# fpga10-serdes-power.net
KiCad netlist of a schematic drawn in Altium Designer
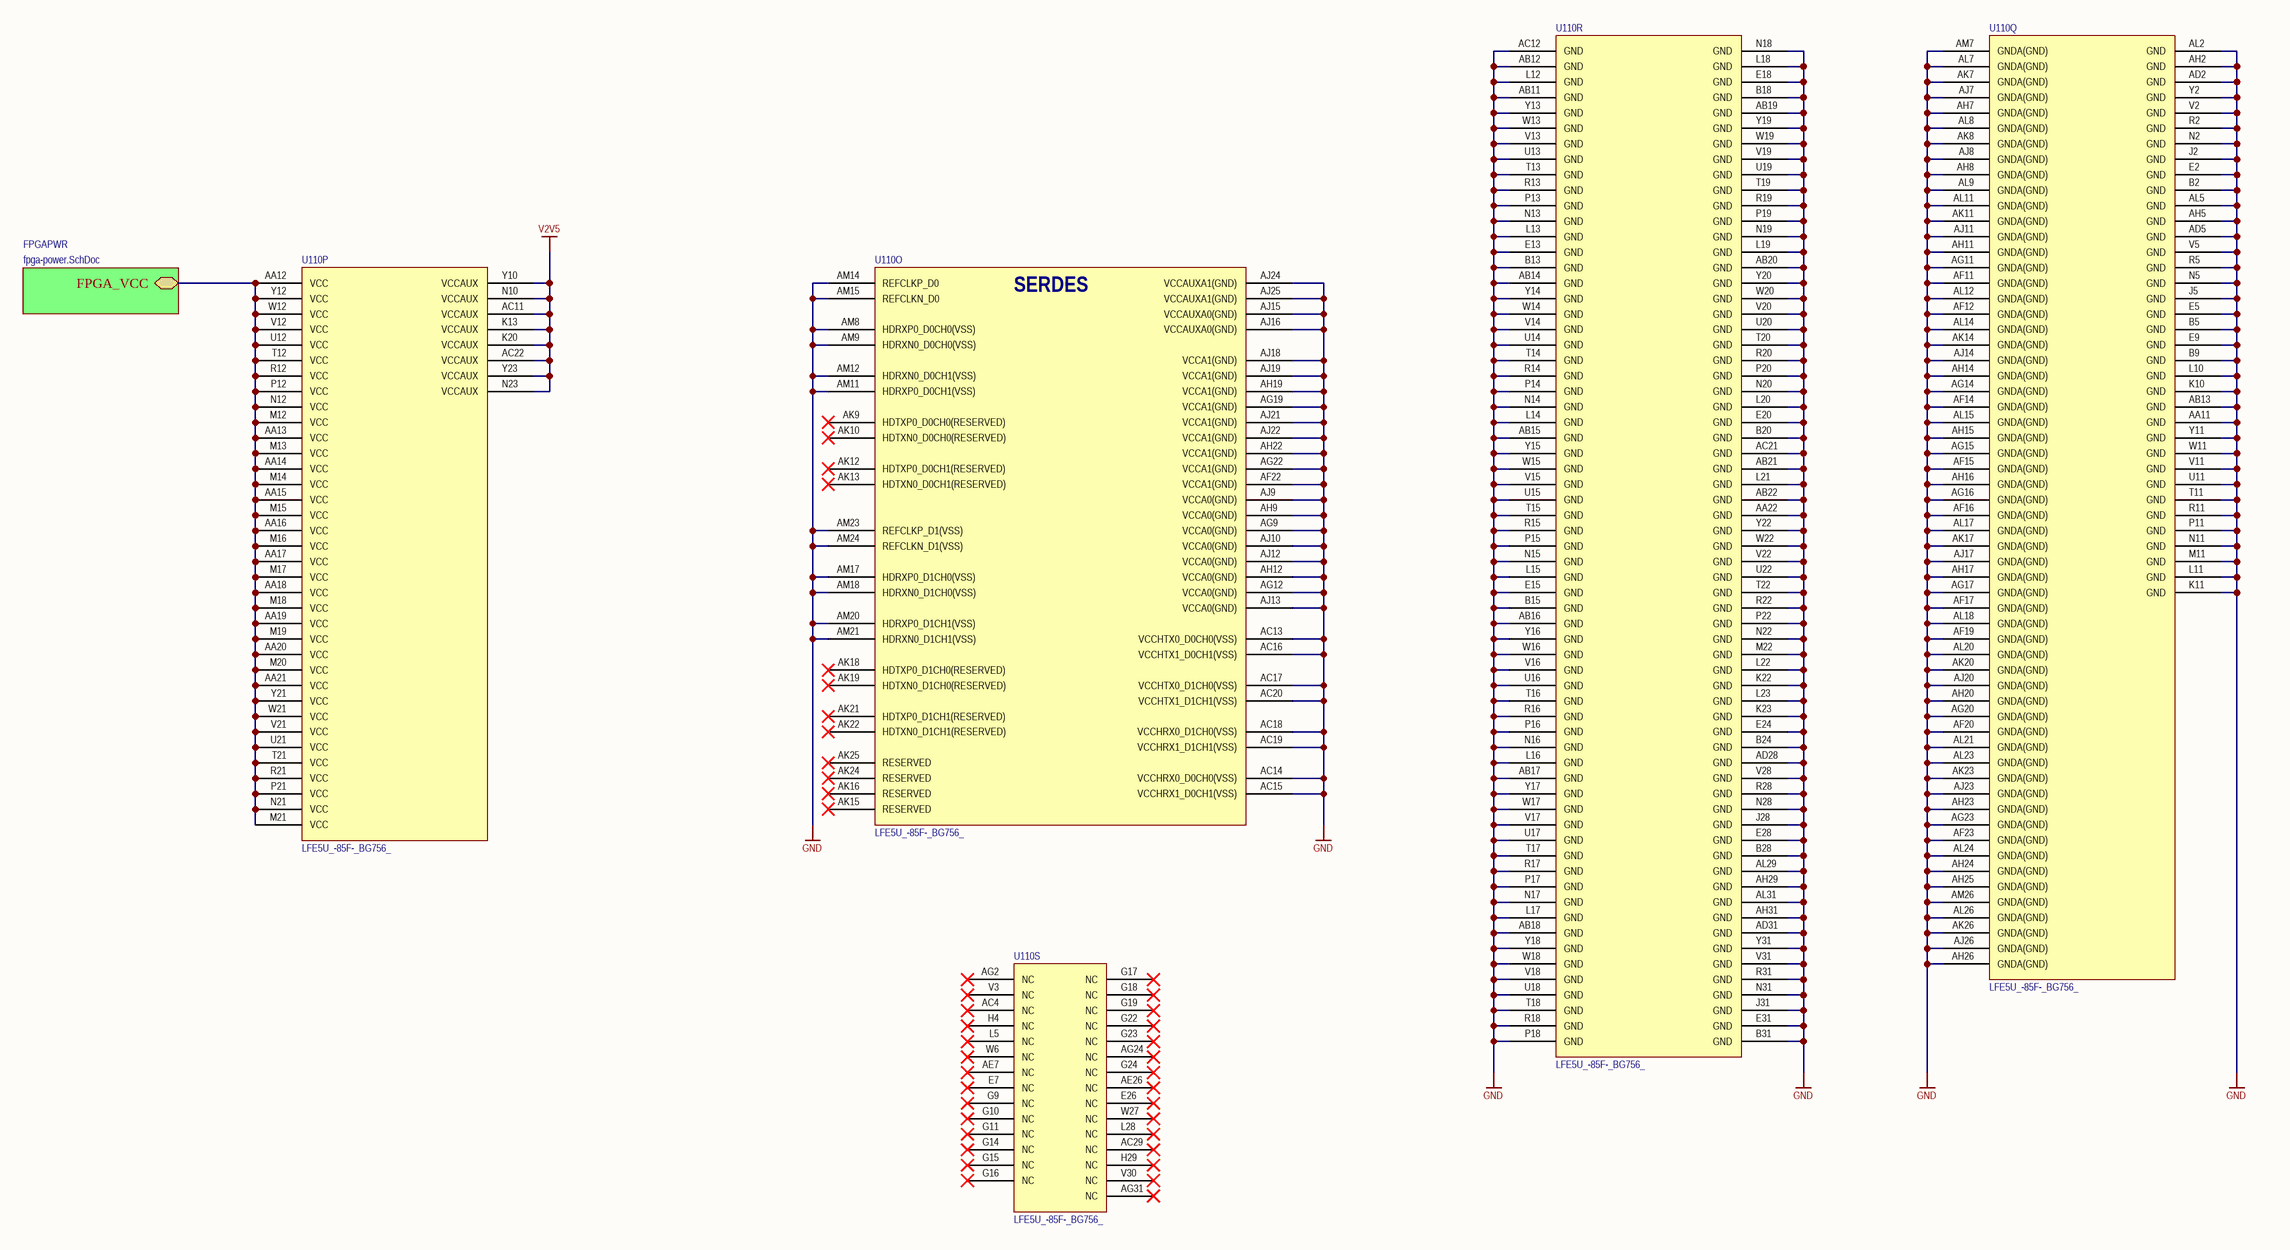
[diagram p0: fpga10-serdes-power.SchDoc]

(export (version "E")
  (design (tool "Eeschema 10.0.6"))
  (components
    (comp (ref "U110")
      (value "LFE5U_-85F-_BG756_")
      (footprint "lattice:caBGA756")
      (description "ECP5 FPGA, 85k LUT, 756-caBGA")
      (fields (field (name "MANUFACTURER") "Lattice Semiconductor"))
      (libsource (lib "lattice") (part "LFE5U_-85F-_BG756_"))
    )
  )
  (nets
    (net (code "1") (name "/FPGA_VCC") (class "Default")
      (node (ref "U110") (pin "AA12") (pinfunction "VCC_AA12") (pintype "power_in"))
      (node (ref "U110") (pin "AA13") (pinfunction "VCC_AA13") (pintype "power_in"))
      (node (ref "U110") (pin "AA14") (pinfunction "VCC_AA14") (pintype "power_in"))
      (node (ref "U110") (pin "AA15") (pinfunction "VCC_AA15") (pintype "power_in"))
      (node (ref "U110") (pin "AA16") (pinfunction "VCC_AA16") (pintype "power_in"))
      (node (ref "U110") (pin "AA17") (pinfunction "VCC_AA17") (pintype "power_in"))
      (node (ref "U110") (pin "AA18") (pinfunction "VCC_AA18") (pintype "power_in"))
      (node (ref "U110") (pin "AA19") (pinfunction "VCC_AA19") (pintype "power_in"))
      (node (ref "U110") (pin "AA20") (pinfunction "VCC_AA20") (pintype "power_in"))
      (node (ref "U110") (pin "AA21") (pinfunction "VCC_AA21") (pintype "power_in"))
      (node (ref "U110") (pin "M12") (pinfunction "VCC_M12") (pintype "power_in"))
      (node (ref "U110") (pin "M13") (pinfunction "VCC_M13") (pintype "power_in"))
      (node (ref "U110") (pin "M14") (pinfunction "VCC_M14") (pintype "power_in"))
      (node (ref "U110") (pin "M15") (pinfunction "VCC_M15") (pintype "power_in"))
      (node (ref "U110") (pin "M16") (pinfunction "VCC_M16") (pintype "power_in"))
      (node (ref "U110") (pin "M17") (pinfunction "VCC_M17") (pintype "power_in"))
      (node (ref "U110") (pin "M18") (pinfunction "VCC_M18") (pintype "power_in"))
      (node (ref "U110") (pin "M19") (pinfunction "VCC_M19") (pintype "power_in"))
      (node (ref "U110") (pin "M20") (pinfunction "VCC_M20") (pintype "power_in"))
      (node (ref "U110") (pin "M21") (pinfunction "VCC_M21") (pintype "power_in"))
      (node (ref "U110") (pin "N12") (pinfunction "VCC_N12") (pintype "power_in"))
      (node (ref "U110") (pin "N21") (pinfunction "VCC_N21") (pintype "power_in"))
      (node (ref "U110") (pin "P12") (pinfunction "VCC_P12") (pintype "power_in"))
      (node (ref "U110") (pin "P21") (pinfunction "VCC_P21") (pintype "power_in"))
      (node (ref "U110") (pin "R12") (pinfunction "VCC_R12") (pintype "power_in"))
      (node (ref "U110") (pin "R21") (pinfunction "VCC_R21") (pintype "power_in"))
      (node (ref "U110") (pin "T12") (pinfunction "VCC_T12") (pintype "power_in"))
      (node (ref "U110") (pin "T21") (pinfunction "VCC_T21") (pintype "power_in"))
      (node (ref "U110") (pin "U12") (pinfunction "VCC_U12") (pintype "power_in"))
      (node (ref "U110") (pin "U21") (pinfunction "VCC_U21") (pintype "power_in"))
      (node (ref "U110") (pin "V12") (pinfunction "VCC_V12") (pintype "power_in"))
      (node (ref "U110") (pin "V21") (pinfunction "VCC_V21") (pintype "power_in"))
      (node (ref "U110") (pin "W12") (pinfunction "VCC_W12") (pintype "power_in"))
      (node (ref "U110") (pin "W21") (pinfunction "VCC_W21") (pintype "power_in"))
      (node (ref "U110") (pin "Y12") (pinfunction "VCC_Y12") (pintype "power_in"))
      (node (ref "U110") (pin "Y21") (pinfunction "VCC_Y21") (pintype "power_in"))
    )
    (net (code "2") (name "GND") (class "Default")
      (node (ref "U110") (pin "AA11") (pinfunction "GND_AA11") (pintype "power_in"))
      (node (ref "U110") (pin "AA22") (pinfunction "GND_AA22") (pintype "power_in"))
      (node (ref "U110") (pin "AB11") (pinfunction "GND_AB11") (pintype "power_in"))
      (node (ref "U110") (pin "AB12") (pinfunction "GND_AB12") (pintype "power_in"))
      (node (ref "U110") (pin "AB13") (pinfunction "GND_AB13") (pintype "power_in"))
      (node (ref "U110") (pin "AB14") (pinfunction "GND_AB14") (pintype "power_in"))
      (node (ref "U110") (pin "AB15") (pinfunction "GND_AB15") (pintype "power_in"))
      (node (ref "U110") (pin "AB16") (pinfunction "GND_AB16") (pintype "power_in"))
      (node (ref "U110") (pin "AB17") (pinfunction "GND_AB17") (pintype "power_in"))
      (node (ref "U110") (pin "AB18") (pinfunction "GND_AB18") (pintype "power_in"))
      (node (ref "U110") (pin "AB19") (pinfunction "GND_AB19") (pintype "power_in"))
      (node (ref "U110") (pin "AB20") (pinfunction "GND_AB20") (pintype "power_in"))
      (node (ref "U110") (pin "AB21") (pinfunction "GND_AB21") (pintype "power_in"))
      (node (ref "U110") (pin "AB22") (pinfunction "GND_AB22") (pintype "power_in"))
      (node (ref "U110") (pin "AC12") (pinfunction "GND_AC12") (pintype "power_in"))
      (node (ref "U110") (pin "AC13") (pinfunction "VCCHTX0_D0CH0(VSS)_AC13") (pintype "power_in"))
      (node (ref "U110") (pin "AC14") (pinfunction "VCCHRX0_D0CH0(VSS)_AC14") (pintype "power_in"))
      (node (ref "U110") (pin "AC15") (pinfunction "VCCHRX1_D0CH1(VSS)_AC15") (pintype "power_in"))
      (node (ref "U110") (pin "AC16") (pinfunction "VCCHTX1_D0CH1(VSS)_AC16") (pintype "power_in"))
      (node (ref "U110") (pin "AC17") (pinfunction "VCCHTX0_D1CH0(VSS)_AC17") (pintype "power_in"))
      (node (ref "U110") (pin "AC18") (pinfunction "VCCHRX0_D1CH0(VSS)_AC18") (pintype "power_in"))
      (node (ref "U110") (pin "AC19") (pinfunction "VCCHRX1_D1CH1(VSS)_AC19") (pintype "power_in"))
      (node (ref "U110") (pin "AC20") (pinfunction "VCCHTX1_D1CH1(VSS)_AC20") (pintype "power_in"))
      (node (ref "U110") (pin "AC21") (pinfunction "GND_AC21") (pintype "power_in"))
      (node (ref "U110") (pin "AD2") (pinfunction "GND_AD2") (pintype "power_in"))
      (node (ref "U110") (pin "AD28") (pinfunction "GND_AD28") (pintype "power_in"))
      (node (ref "U110") (pin "AD31") (pinfunction "GND_AD31") (pintype "power_in"))
      (node (ref "U110") (pin "AD5") (pinfunction "GND_AD5") (pintype "power_in"))
      (node (ref "U110") (pin "AF11") (pinfunction "GNDA(GND)_AF11") (pintype "power_in"))
      (node (ref "U110") (pin "AF12") (pinfunction "GNDA(GND)_AF12") (pintype "power_in"))
      (node (ref "U110") (pin "AF14") (pinfunction "GNDA(GND)_AF14") (pintype "power_in"))
      (node (ref "U110") (pin "AF15") (pinfunction "GNDA(GND)_AF15") (pintype "power_in"))
      (node (ref "U110") (pin "AF16") (pinfunction "GNDA(GND)_AF16") (pintype "power_in"))
      (node (ref "U110") (pin "AF17") (pinfunction "GNDA(GND)_AF17") (pintype "power_in"))
      (node (ref "U110") (pin "AF19") (pinfunction "GNDA(GND)_AF19") (pintype "power_in"))
      (node (ref "U110") (pin "AF20") (pinfunction "GNDA(GND)_AF20") (pintype "power_in"))
      (node (ref "U110") (pin "AF22") (pinfunction "VCCA1(GND)_AF22") (pintype "power_in"))
      (node (ref "U110") (pin "AF23") (pinfunction "GNDA(GND)_AF23") (pintype "power_in"))
      (node (ref "U110") (pin "AG11") (pinfunction "GNDA(GND)_AG11") (pintype "power_in"))
      (node (ref "U110") (pin "AG12") (pinfunction "VCCA0(GND)_AG12") (pintype "power_in"))
      (node (ref "U110") (pin "AG14") (pinfunction "GNDA(GND)_AG14") (pintype "power_in"))
      (node (ref "U110") (pin "AG15") (pinfunction "GNDA(GND)_AG15") (pintype "power_in"))
      (node (ref "U110") (pin "AG16") (pinfunction "GNDA(GND)_AG16") (pintype "power_in"))
      (node (ref "U110") (pin "AG17") (pinfunction "GNDA(GND)_AG17") (pintype "power_in"))
      (node (ref "U110") (pin "AG19") (pinfunction "VCCA1(GND)_AG19") (pintype "power_in"))
      (node (ref "U110") (pin "AG20") (pinfunction "GNDA(GND)_AG20") (pintype "power_in"))
      (node (ref "U110") (pin "AG22") (pinfunction "VCCA1(GND)_AG22") (pintype "power_in"))
      (node (ref "U110") (pin "AG23") (pinfunction "GNDA(GND)_AG23") (pintype "power_in"))
      (node (ref "U110") (pin "AG9") (pinfunction "VCCA0(GND)_AG9") (pintype "power_in"))
      (node (ref "U110") (pin "AH11") (pinfunction "GNDA(GND)_AH11") (pintype "power_in"))
      (node (ref "U110") (pin "AH12") (pinfunction "VCCA0(GND)_AH12") (pintype "power_in"))
      (node (ref "U110") (pin "AH14") (pinfunction "GNDA(GND)_AH14") (pintype "power_in"))
      (node (ref "U110") (pin "AH15") (pinfunction "GNDA(GND)_AH15") (pintype "power_in"))
      (node (ref "U110") (pin "AH16") (pinfunction "GNDA(GND)_AH16") (pintype "power_in"))
      (node (ref "U110") (pin "AH17") (pinfunction "GNDA(GND)_AH17") (pintype "power_in"))
      (node (ref "U110") (pin "AH19") (pinfunction "VCCA1(GND)_AH19") (pintype "power_in"))
      (node (ref "U110") (pin "AH2") (pinfunction "GND_AH2") (pintype "power_in"))
      (node (ref "U110") (pin "AH20") (pinfunction "GNDA(GND)_AH20") (pintype "power_in"))
      (node (ref "U110") (pin "AH22") (pinfunction "VCCA1(GND)_AH22") (pintype "power_in"))
      (node (ref "U110") (pin "AH23") (pinfunction "GNDA(GND)_AH23") (pintype "power_in"))
      (node (ref "U110") (pin "AH24") (pinfunction "GNDA(GND)_AH24") (pintype "power_in"))
      (node (ref "U110") (pin "AH25") (pinfunction "GNDA(GND)_AH25") (pintype "power_in"))
      (node (ref "U110") (pin "AH26") (pinfunction "GNDA(GND)_AH26") (pintype "power_in"))
      (node (ref "U110") (pin "AH29") (pinfunction "GND_AH29") (pintype "power_in"))
      (node (ref "U110") (pin "AH31") (pinfunction "GND_AH31") (pintype "power_in"))
      (node (ref "U110") (pin "AH5") (pinfunction "GND_AH5") (pintype "power_in"))
      (node (ref "U110") (pin "AH7") (pinfunction "GNDA(GND)_AH7") (pintype "power_in"))
      (node (ref "U110") (pin "AH8") (pinfunction "GNDA(GND)_AH8") (pintype "power_in"))
      (node (ref "U110") (pin "AH9") (pinfunction "VCCA0(GND)_AH9") (pintype "power_in"))
      (node (ref "U110") (pin "AJ10") (pinfunction "VCCA0(GND)_AJ10") (pintype "power_in"))
      (node (ref "U110") (pin "AJ11") (pinfunction "GNDA(GND)_AJ11") (pintype "power_in"))
      (node (ref "U110") (pin "AJ12") (pinfunction "VCCA0(GND)_AJ12") (pintype "power_in"))
      (node (ref "U110") (pin "AJ13") (pinfunction "VCCA0(GND)_AJ13") (pintype "power_in"))
      (node (ref "U110") (pin "AJ14") (pinfunction "GNDA(GND)_AJ14") (pintype "power_in"))
      (node (ref "U110") (pin "AJ15") (pinfunction "VCCAUXA0(GND)_AJ15") (pintype "power_in"))
      (node (ref "U110") (pin "AJ16") (pinfunction "VCCAUXA0(GND)_AJ16") (pintype "power_in"))
      (node (ref "U110") (pin "AJ17") (pinfunction "GNDA(GND)_AJ17") (pintype "power_in"))
      (node (ref "U110") (pin "AJ18") (pinfunction "VCCA1(GND)_AJ18") (pintype "power_in"))
      (node (ref "U110") (pin "AJ19") (pinfunction "VCCA1(GND)_AJ19") (pintype "power_in"))
      (node (ref "U110") (pin "AJ20") (pinfunction "GNDA(GND)_AJ20") (pintype "power_in"))
      (node (ref "U110") (pin "AJ21") (pinfunction "VCCA1(GND)_AJ21") (pintype "power_in"))
      (node (ref "U110") (pin "AJ22") (pinfunction "VCCA1(GND)_AJ22") (pintype "power_in"))
      (node (ref "U110") (pin "AJ23") (pinfunction "GNDA(GND)_AJ23") (pintype "power_in"))
      (node (ref "U110") (pin "AJ24") (pinfunction "VCCAUXA1(GND)_AJ24") (pintype "power_in"))
      (node (ref "U110") (pin "AJ25") (pinfunction "VCCAUXA1(GND)_AJ25") (pintype "power_in"))
      (node (ref "U110") (pin "AJ26") (pinfunction "GNDA(GND)_AJ26") (pintype "power_in"))
      (node (ref "U110") (pin "AJ7") (pinfunction "GNDA(GND)_AJ7") (pintype "power_in"))
      (node (ref "U110") (pin "AJ8") (pinfunction "GNDA(GND)_AJ8") (pintype "power_in"))
      (node (ref "U110") (pin "AJ9") (pinfunction "VCCA0(GND)_AJ9") (pintype "power_in"))
      (node (ref "U110") (pin "AK11") (pinfunction "GNDA(GND)_AK11") (pintype "power_in"))
      (node (ref "U110") (pin "AK14") (pinfunction "GNDA(GND)_AK14") (pintype "power_in"))
      (node (ref "U110") (pin "AK17") (pinfunction "GNDA(GND)_AK17") (pintype "power_in"))
      (node (ref "U110") (pin "AK20") (pinfunction "GNDA(GND)_AK20") (pintype "power_in"))
      (node (ref "U110") (pin "AK23") (pinfunction "GNDA(GND)_AK23") (pintype "power_in"))
      (node (ref "U110") (pin "AK26") (pinfunction "GNDA(GND)_AK26") (pintype "power_in"))
      (node (ref "U110") (pin "AK7") (pinfunction "GNDA(GND)_AK7") (pintype "power_in"))
      (node (ref "U110") (pin "AK8") (pinfunction "GNDA(GND)_AK8") (pintype "power_in"))
      (node (ref "U110") (pin "AL11") (pinfunction "GNDA(GND)_AL11") (pintype "power_in"))
      (node (ref "U110") (pin "AL12") (pinfunction "GNDA(GND)_AL12") (pintype "power_in"))
      (node (ref "U110") (pin "AL14") (pinfunction "GNDA(GND)_AL14") (pintype "power_in"))
      (node (ref "U110") (pin "AL15") (pinfunction "GNDA(GND)_AL15") (pintype "power_in"))
      (node (ref "U110") (pin "AL17") (pinfunction "GNDA(GND)_AL17") (pintype "power_in"))
      (node (ref "U110") (pin "AL18") (pinfunction "GNDA(GND)_AL18") (pintype "power_in"))
      (node (ref "U110") (pin "AL2") (pinfunction "GND_AL2") (pintype "power_in"))
      (node (ref "U110") (pin "AL20") (pinfunction "GNDA(GND)_AL20") (pintype "power_in"))
      (node (ref "U110") (pin "AL21") (pinfunction "GNDA(GND)_AL21") (pintype "power_in"))
      (node (ref "U110") (pin "AL23") (pinfunction "GNDA(GND)_AL23") (pintype "power_in"))
      (node (ref "U110") (pin "AL24") (pinfunction "GNDA(GND)_AL24") (pintype "power_in"))
      (node (ref "U110") (pin "AL26") (pinfunction "GNDA(GND)_AL26") (pintype "power_in"))
      (node (ref "U110") (pin "AL29") (pinfunction "GND_AL29") (pintype "power_in"))
      (node (ref "U110") (pin "AL31") (pinfunction "GND_AL31") (pintype "power_in"))
      (node (ref "U110") (pin "AL5") (pinfunction "GND_AL5") (pintype "power_in"))
      (node (ref "U110") (pin "AL7") (pinfunction "GNDA(GND)_AL7") (pintype "power_in"))
      (node (ref "U110") (pin "AL8") (pinfunction "GNDA(GND)_AL8") (pintype "power_in"))
      (node (ref "U110") (pin "AL9") (pinfunction "GNDA(GND)_AL9") (pintype "power_in"))
      (node (ref "U110") (pin "AM11") (pinfunction "HDRXP0_D0CH1(VSS)_AM11") (pintype "passive"))
      (node (ref "U110") (pin "AM12") (pinfunction "HDRXN0_D0CH1(VSS)_AM12") (pintype "passive"))
      (node (ref "U110") (pin "AM14") (pinfunction "REFCLKP_D0_AM14") (pintype "passive"))
      (node (ref "U110") (pin "AM15") (pinfunction "REFCLKN_D0_AM15") (pintype "passive"))
      (node (ref "U110") (pin "AM17") (pinfunction "HDRXP0_D1CH0(VSS)_AM17") (pintype "passive"))
      (node (ref "U110") (pin "AM18") (pinfunction "HDRXN0_D1CH0(VSS)_AM18") (pintype "passive"))
      (node (ref "U110") (pin "AM20") (pinfunction "HDRXP0_D1CH1(VSS)_AM20") (pintype "passive"))
      (node (ref "U110") (pin "AM21") (pinfunction "HDRXN0_D1CH1(VSS)_AM21") (pintype "passive"))
      (node (ref "U110") (pin "AM23") (pinfunction "REFCLKP_D1(VSS)_AM23") (pintype "passive"))
      (node (ref "U110") (pin "AM24") (pinfunction "REFCLKN_D1(VSS)_AM24") (pintype "passive"))
      (node (ref "U110") (pin "AM26") (pinfunction "GNDA(GND)_AM26") (pintype "power_in"))
      (node (ref "U110") (pin "AM7") (pinfunction "GNDA(GND)_AM7") (pintype "power_in"))
      (node (ref "U110") (pin "AM8") (pinfunction "HDRXP0_D0CH0(VSS)_AM8") (pintype "passive"))
      (node (ref "U110") (pin "AM9") (pinfunction "HDRXN0_D0CH0(VSS)_AM9") (pintype "passive"))
      (node (ref "U110") (pin "B13") (pinfunction "GND_B13") (pintype "power_in"))
      (node (ref "U110") (pin "B15") (pinfunction "GND_B15") (pintype "power_in"))
      (node (ref "U110") (pin "B18") (pinfunction "GND_B18") (pintype "power_in"))
      (node (ref "U110") (pin "B2") (pinfunction "GND_B2") (pintype "power_in"))
      (node (ref "U110") (pin "B20") (pinfunction "GND_B20") (pintype "power_in"))
      (node (ref "U110") (pin "B24") (pinfunction "GND_B24") (pintype "power_in"))
      (node (ref "U110") (pin "B28") (pinfunction "GND_B28") (pintype "power_in"))
      (node (ref "U110") (pin "B31") (pinfunction "GND_B31") (pintype "power_in"))
      (node (ref "U110") (pin "B5") (pinfunction "GND_B5") (pintype "power_in"))
      (node (ref "U110") (pin "B9") (pinfunction "GND_B9") (pintype "power_in"))
      (node (ref "U110") (pin "E13") (pinfunction "GND_E13") (pintype "power_in"))
      (node (ref "U110") (pin "E15") (pinfunction "GND_E15") (pintype "power_in"))
      (node (ref "U110") (pin "E18") (pinfunction "GND_E18") (pintype "power_in"))
      (node (ref "U110") (pin "E2") (pinfunction "GND_E2") (pintype "power_in"))
      (node (ref "U110") (pin "E20") (pinfunction "GND_E20") (pintype "power_in"))
      (node (ref "U110") (pin "E24") (pinfunction "GND_E24") (pintype "power_in"))
      (node (ref "U110") (pin "E28") (pinfunction "GND_E28") (pintype "power_in"))
      (node (ref "U110") (pin "E31") (pinfunction "GND_E31") (pintype "power_in"))
      (node (ref "U110") (pin "E5") (pinfunction "GND_E5") (pintype "power_in"))
      (node (ref "U110") (pin "E9") (pinfunction "GND_E9") (pintype "power_in"))
      (node (ref "U110") (pin "J2") (pinfunction "GND_J2") (pintype "power_in"))
      (node (ref "U110") (pin "J28") (pinfunction "GND_J28") (pintype "power_in"))
      (node (ref "U110") (pin "J31") (pinfunction "GND_J31") (pintype "power_in"))
      (node (ref "U110") (pin "J5") (pinfunction "GND_J5") (pintype "power_in"))
      (node (ref "U110") (pin "K10") (pinfunction "GND_K10") (pintype "power_in"))
      (node (ref "U110") (pin "K11") (pinfunction "GND_K11") (pintype "power_in"))
      (node (ref "U110") (pin "K22") (pinfunction "GND_K22") (pintype "power_in"))
      (node (ref "U110") (pin "K23") (pinfunction "GND_K23") (pintype "power_in"))
      (node (ref "U110") (pin "L10") (pinfunction "GND_L10") (pintype "power_in"))
      (node (ref "U110") (pin "L11") (pinfunction "GND_L11") (pintype "power_in"))
      (node (ref "U110") (pin "L12") (pinfunction "GND_L12") (pintype "power_in"))
      (node (ref "U110") (pin "L13") (pinfunction "GND_L13") (pintype "power_in"))
      (node (ref "U110") (pin "L14") (pinfunction "GND_L14") (pintype "power_in"))
      (node (ref "U110") (pin "L15") (pinfunction "GND_L15") (pintype "power_in"))
      (node (ref "U110") (pin "L16") (pinfunction "GND_L16") (pintype "power_in"))
      (node (ref "U110") (pin "L17") (pinfunction "GND_L17") (pintype "power_in"))
      (node (ref "U110") (pin "L18") (pinfunction "GND_L18") (pintype "power_in"))
      (node (ref "U110") (pin "L19") (pinfunction "GND_L19") (pintype "power_in"))
      (node (ref "U110") (pin "L20") (pinfunction "GND_L20") (pintype "power_in"))
      (node (ref "U110") (pin "L21") (pinfunction "GND_L21") (pintype "power_in"))
      (node (ref "U110") (pin "L22") (pinfunction "GND_L22") (pintype "power_in"))
      (node (ref "U110") (pin "L23") (pinfunction "GND_L23") (pintype "power_in"))
      (node (ref "U110") (pin "M11") (pinfunction "GND_M11") (pintype "power_in"))
      (node (ref "U110") (pin "M22") (pinfunction "GND_M22") (pintype "power_in"))
      (node (ref "U110") (pin "N11") (pinfunction "GND_N11") (pintype "power_in"))
      (node (ref "U110") (pin "N13") (pinfunction "GND_N13") (pintype "power_in"))
      (node (ref "U110") (pin "N14") (pinfunction "GND_N14") (pintype "power_in"))
      (node (ref "U110") (pin "N15") (pinfunction "GND_N15") (pintype "power_in"))
      (node (ref "U110") (pin "N16") (pinfunction "GND_N16") (pintype "power_in"))
      (node (ref "U110") (pin "N17") (pinfunction "GND_N17") (pintype "power_in"))
      (node (ref "U110") (pin "N18") (pinfunction "GND_N18") (pintype "power_in"))
      (node (ref "U110") (pin "N19") (pinfunction "GND_N19") (pintype "power_in"))
      (node (ref "U110") (pin "N2") (pinfunction "GND_N2") (pintype "power_in"))
      (node (ref "U110") (pin "N20") (pinfunction "GND_N20") (pintype "power_in"))
      (node (ref "U110") (pin "N22") (pinfunction "GND_N22") (pintype "power_in"))
      (node (ref "U110") (pin "N28") (pinfunction "GND_N28") (pintype "power_in"))
      (node (ref "U110") (pin "N31") (pinfunction "GND_N31") (pintype "power_in"))
      (node (ref "U110") (pin "N5") (pinfunction "GND_N5") (pintype "power_in"))
      (node (ref "U110") (pin "P11") (pinfunction "GND_P11") (pintype "power_in"))
      (node (ref "U110") (pin "P13") (pinfunction "GND_P13") (pintype "power_in"))
      (node (ref "U110") (pin "P14") (pinfunction "GND_P14") (pintype "power_in"))
      (node (ref "U110") (pin "P15") (pinfunction "GND_P15") (pintype "power_in"))
      (node (ref "U110") (pin "P16") (pinfunction "GND_P16") (pintype "power_in"))
      (node (ref "U110") (pin "P17") (pinfunction "GND_P17") (pintype "power_in"))
      (node (ref "U110") (pin "P18") (pinfunction "GND_P18") (pintype "power_in"))
      (node (ref "U110") (pin "P19") (pinfunction "GND_P19") (pintype "power_in"))
      (node (ref "U110") (pin "P20") (pinfunction "GND_P20") (pintype "power_in"))
      (node (ref "U110") (pin "P22") (pinfunction "GND_P22") (pintype "power_in"))
      (node (ref "U110") (pin "R11") (pinfunction "GND_R11") (pintype "power_in"))
      (node (ref "U110") (pin "R13") (pinfunction "GND_R13") (pintype "power_in"))
      (node (ref "U110") (pin "R14") (pinfunction "GND_R14") (pintype "power_in"))
      (node (ref "U110") (pin "R15") (pinfunction "GND_R15") (pintype "power_in"))
      (node (ref "U110") (pin "R16") (pinfunction "GND_R16") (pintype "power_in"))
      (node (ref "U110") (pin "R17") (pinfunction "GND_R17") (pintype "power_in"))
      (node (ref "U110") (pin "R18") (pinfunction "GND_R18") (pintype "power_in"))
      (node (ref "U110") (pin "R19") (pinfunction "GND_R19") (pintype "power_in"))
      (node (ref "U110") (pin "R2") (pinfunction "GND_R2") (pintype "power_in"))
      (node (ref "U110") (pin "R20") (pinfunction "GND_R20") (pintype "power_in"))
      (node (ref "U110") (pin "R22") (pinfunction "GND_R22") (pintype "power_in"))
      (node (ref "U110") (pin "R28") (pinfunction "GND_R28") (pintype "power_in"))
      (node (ref "U110") (pin "R31") (pinfunction "GND_R31") (pintype "power_in"))
      (node (ref "U110") (pin "R5") (pinfunction "GND_R5") (pintype "power_in"))
      (node (ref "U110") (pin "T11") (pinfunction "GND_T11") (pintype "power_in"))
      (node (ref "U110") (pin "T13") (pinfunction "GND_T13") (pintype "power_in"))
      (node (ref "U110") (pin "T14") (pinfunction "GND_T14") (pintype "power_in"))
      (node (ref "U110") (pin "T15") (pinfunction "GND_T15") (pintype "power_in"))
      (node (ref "U110") (pin "T16") (pinfunction "GND_T16") (pintype "power_in"))
      (node (ref "U110") (pin "T17") (pinfunction "GND_T17") (pintype "power_in"))
      (node (ref "U110") (pin "T18") (pinfunction "GND_T18") (pintype "power_in"))
      (node (ref "U110") (pin "T19") (pinfunction "GND_T19") (pintype "power_in"))
      (node (ref "U110") (pin "T20") (pinfunction "GND_T20") (pintype "power_in"))
      (node (ref "U110") (pin "T22") (pinfunction "GND_T22") (pintype "power_in"))
      (node (ref "U110") (pin "U11") (pinfunction "GND_U11") (pintype "power_in"))
      (node (ref "U110") (pin "U13") (pinfunction "GND_U13") (pintype "power_in"))
      (node (ref "U110") (pin "U14") (pinfunction "GND_U14") (pintype "power_in"))
      (node (ref "U110") (pin "U15") (pinfunction "GND_U15") (pintype "power_in"))
      (node (ref "U110") (pin "U16") (pinfunction "GND_U16") (pintype "power_in"))
      (node (ref "U110") (pin "U17") (pinfunction "GND_U17") (pintype "power_in"))
      (node (ref "U110") (pin "U18") (pinfunction "GND_U18") (pintype "power_in"))
      (node (ref "U110") (pin "U19") (pinfunction "GND_U19") (pintype "power_in"))
      (node (ref "U110") (pin "U20") (pinfunction "GND_U20") (pintype "power_in"))
      (node (ref "U110") (pin "U22") (pinfunction "GND_U22") (pintype "power_in"))
      (node (ref "U110") (pin "V11") (pinfunction "GND_V11") (pintype "power_in"))
      (node (ref "U110") (pin "V13") (pinfunction "GND_V13") (pintype "power_in"))
      (node (ref "U110") (pin "V14") (pinfunction "GND_V14") (pintype "power_in"))
      (node (ref "U110") (pin "V15") (pinfunction "GND_V15") (pintype "power_in"))
      (node (ref "U110") (pin "V16") (pinfunction "GND_V16") (pintype "power_in"))
      (node (ref "U110") (pin "V17") (pinfunction "GND_V17") (pintype "power_in"))
      (node (ref "U110") (pin "V18") (pinfunction "GND_V18") (pintype "power_in"))
      (node (ref "U110") (pin "V19") (pinfunction "GND_V19") (pintype "power_in"))
      (node (ref "U110") (pin "V2") (pinfunction "GND_V2") (pintype "power_in"))
      (node (ref "U110") (pin "V20") (pinfunction "GND_V20") (pintype "power_in"))
      (node (ref "U110") (pin "V22") (pinfunction "GND_V22") (pintype "power_in"))
      (node (ref "U110") (pin "V28") (pinfunction "GND_V28") (pintype "power_in"))
      (node (ref "U110") (pin "V31") (pinfunction "GND_V31") (pintype "power_in"))
      (node (ref "U110") (pin "V5") (pinfunction "GND_V5") (pintype "power_in"))
      (node (ref "U110") (pin "W11") (pinfunction "GND_W11") (pintype "power_in"))
      (node (ref "U110") (pin "W13") (pinfunction "GND_W13") (pintype "power_in"))
      (node (ref "U110") (pin "W14") (pinfunction "GND_W14") (pintype "power_in"))
      (node (ref "U110") (pin "W15") (pinfunction "GND_W15") (pintype "power_in"))
      (node (ref "U110") (pin "W16") (pinfunction "GND_W16") (pintype "power_in"))
      (node (ref "U110") (pin "W17") (pinfunction "GND_W17") (pintype "power_in"))
      (node (ref "U110") (pin "W18") (pinfunction "GND_W18") (pintype "power_in"))
      (node (ref "U110") (pin "W19") (pinfunction "GND_W19") (pintype "power_in"))
      (node (ref "U110") (pin "W20") (pinfunction "GND_W20") (pintype "power_in"))
      (node (ref "U110") (pin "W22") (pinfunction "GND_W22") (pintype "power_in"))
      (node (ref "U110") (pin "Y11") (pinfunction "GND_Y11") (pintype "power_in"))
      (node (ref "U110") (pin "Y13") (pinfunction "GND_Y13") (pintype "power_in"))
      (node (ref "U110") (pin "Y14") (pinfunction "GND_Y14") (pintype "power_in"))
      (node (ref "U110") (pin "Y15") (pinfunction "GND_Y15") (pintype "power_in"))
      (node (ref "U110") (pin "Y16") (pinfunction "GND_Y16") (pintype "power_in"))
      (node (ref "U110") (pin "Y17") (pinfunction "GND_Y17") (pintype "power_in"))
      (node (ref "U110") (pin "Y18") (pinfunction "GND_Y18") (pintype "power_in"))
      (node (ref "U110") (pin "Y19") (pinfunction "GND_Y19") (pintype "power_in"))
      (node (ref "U110") (pin "Y2") (pinfunction "GND_Y2") (pintype "power_in"))
      (node (ref "U110") (pin "Y20") (pinfunction "GND_Y20") (pintype "power_in"))
      (node (ref "U110") (pin "Y22") (pinfunction "GND_Y22") (pintype "power_in"))
      (node (ref "U110") (pin "Y31") (pinfunction "GND_Y31") (pintype "power_in"))
    )
    (net (code "3") (name "V2V5") (class "Default")
      (node (ref "U110") (pin "AC11") (pinfunction "VCCAUX_AC11") (pintype "power_in"))
      (node (ref "U110") (pin "AC22") (pinfunction "VCCAUX_AC22") (pintype "power_in"))
      (node (ref "U110") (pin "K13") (pinfunction "VCCAUX_K13") (pintype "power_in"))
      (node (ref "U110") (pin "K20") (pinfunction "VCCAUX_K20") (pintype "power_in"))
      (node (ref "U110") (pin "N10") (pinfunction "VCCAUX_N10") (pintype "power_in"))
      (node (ref "U110") (pin "N23") (pinfunction "VCCAUX_N23") (pintype "power_in"))
      (node (ref "U110") (pin "Y10") (pinfunction "VCCAUX_Y10") (pintype "power_in"))
      (node (ref "U110") (pin "Y23") (pinfunction "VCCAUX_Y23") (pintype "power_in"))
    )
    (net (code "4") (name "unconnected-(U110O-HDTXN0_D0CH0(RESERVED)-PadAK10)") (class "Default")
      (node (ref "U110") (pin "AK10") (pinfunction "HDTXN0_D0CH0(RESERVED)_AK10") (pintype "passive+no_connect"))
    )
    (net (code "5") (name "unconnected-(U110O-HDTXN0_D0CH1(RESERVED)-PadAK13)") (class "Default")
      (node (ref "U110") (pin "AK13") (pinfunction "HDTXN0_D0CH1(RESERVED)_AK13") (pintype "passive+no_connect"))
    )
    (net (code "6") (name "unconnected-(U110O-HDTXN0_D1CH0(RESERVED)-PadAK19)") (class "Default")
      (node (ref "U110") (pin "AK19") (pinfunction "HDTXN0_D1CH0(RESERVED)_AK19") (pintype "passive+no_connect"))
    )
    (net (code "7") (name "unconnected-(U110O-HDTXN0_D1CH1(RESERVED)-PadAK22)") (class "Default")
      (node (ref "U110") (pin "AK22") (pinfunction "HDTXN0_D1CH1(RESERVED)_AK22") (pintype "passive+no_connect"))
    )
    (net (code "8") (name "unconnected-(U110O-HDTXP0_D0CH0(RESERVED)-PadAK9)") (class "Default")
      (node (ref "U110") (pin "AK9") (pinfunction "HDTXP0_D0CH0(RESERVED)_AK9") (pintype "passive+no_connect"))
    )
    (net (code "9") (name "unconnected-(U110O-HDTXP0_D0CH1(RESERVED)-PadAK12)") (class "Default")
      (node (ref "U110") (pin "AK12") (pinfunction "HDTXP0_D0CH1(RESERVED)_AK12") (pintype "passive+no_connect"))
    )
    (net (code "10") (name "unconnected-(U110O-HDTXP0_D1CH0(RESERVED)-PadAK18)") (class "Default")
      (node (ref "U110") (pin "AK18") (pinfunction "HDTXP0_D1CH0(RESERVED)_AK18") (pintype "passive+no_connect"))
    )
    (net (code "11") (name "unconnected-(U110O-HDTXP0_D1CH1(RESERVED)-PadAK21)") (class "Default")
      (node (ref "U110") (pin "AK21") (pinfunction "HDTXP0_D1CH1(RESERVED)_AK21") (pintype "passive+no_connect"))
    )
    (net (code "12") (name "unconnected-(U110O-RESERVED-PadAK15)") (class "Default")
      (node (ref "U110") (pin "AK15") (pinfunction "RESERVED_AK15") (pintype "passive+no_connect"))
    )
    (net (code "13") (name "unconnected-(U110O-RESERVED-PadAK16)") (class "Default")
      (node (ref "U110") (pin "AK16") (pinfunction "RESERVED_AK16") (pintype "passive+no_connect"))
    )
    (net (code "14") (name "unconnected-(U110O-RESERVED-PadAK24)") (class "Default")
      (node (ref "U110") (pin "AK24") (pinfunction "RESERVED_AK24") (pintype "passive+no_connect"))
    )
    (net (code "15") (name "unconnected-(U110O-RESERVED-PadAK25)") (class "Default")
      (node (ref "U110") (pin "AK25") (pinfunction "RESERVED_AK25") (pintype "passive+no_connect"))
    )
    (net (code "16") (name "unconnected-(U110S-NC-PadAC4)") (class "Default")
      (node (ref "U110") (pin "AC4") (pinfunction "NC_AC4") (pintype "passive+no_connect"))
    )
    (net (code "17") (name "unconnected-(U110S-NC-PadAC29)") (class "Default")
      (node (ref "U110") (pin "AC29") (pinfunction "NC_AC29") (pintype "passive+no_connect"))
    )
    (net (code "18") (name "unconnected-(U110S-NC-PadAE7)") (class "Default")
      (node (ref "U110") (pin "AE7") (pinfunction "NC_AE7") (pintype "passive+no_connect"))
    )
    (net (code "19") (name "unconnected-(U110S-NC-PadAE26)") (class "Default")
      (node (ref "U110") (pin "AE26") (pinfunction "NC_AE26") (pintype "passive+no_connect"))
    )
    (net (code "20") (name "unconnected-(U110S-NC-PadAG2)") (class "Default")
      (node (ref "U110") (pin "AG2") (pinfunction "NC_AG2") (pintype "passive+no_connect"))
    )
    (net (code "21") (name "unconnected-(U110S-NC-PadAG24)") (class "Default")
      (node (ref "U110") (pin "AG24") (pinfunction "NC_AG24") (pintype "passive+no_connect"))
    )
    (net (code "22") (name "unconnected-(U110S-NC-PadAG31)") (class "Default")
      (node (ref "U110") (pin "AG31") (pinfunction "NC_AG31") (pintype "passive+no_connect"))
    )
    (net (code "23") (name "unconnected-(U110S-NC-PadE7)") (class "Default")
      (node (ref "U110") (pin "E7") (pinfunction "NC_E7") (pintype "passive+no_connect"))
    )
    (net (code "24") (name "unconnected-(U110S-NC-PadE26)") (class "Default")
      (node (ref "U110") (pin "E26") (pinfunction "NC_E26") (pintype "passive+no_connect"))
    )
    (net (code "25") (name "unconnected-(U110S-NC-PadG9)") (class "Default")
      (node (ref "U110") (pin "G9") (pinfunction "NC_G9") (pintype "passive+no_connect"))
    )
    (net (code "26") (name "unconnected-(U110S-NC-PadG10)") (class "Default")
      (node (ref "U110") (pin "G10") (pinfunction "NC_G10") (pintype "passive+no_connect"))
    )
    (net (code "27") (name "unconnected-(U110S-NC-PadG11)") (class "Default")
      (node (ref "U110") (pin "G11") (pinfunction "NC_G11") (pintype "passive+no_connect"))
    )
    (net (code "28") (name "unconnected-(U110S-NC-PadG14)") (class "Default")
      (node (ref "U110") (pin "G14") (pinfunction "NC_G14") (pintype "passive+no_connect"))
    )
    (net (code "29") (name "unconnected-(U110S-NC-PadG15)") (class "Default")
      (node (ref "U110") (pin "G15") (pinfunction "NC_G15") (pintype "passive+no_connect"))
    )
    (net (code "30") (name "unconnected-(U110S-NC-PadG16)") (class "Default")
      (node (ref "U110") (pin "G16") (pinfunction "NC_G16") (pintype "passive+no_connect"))
    )
    (net (code "31") (name "unconnected-(U110S-NC-PadG17)") (class "Default")
      (node (ref "U110") (pin "G17") (pinfunction "NC_G17") (pintype "passive+no_connect"))
    )
    (net (code "32") (name "unconnected-(U110S-NC-PadG18)") (class "Default")
      (node (ref "U110") (pin "G18") (pinfunction "NC_G18") (pintype "passive+no_connect"))
    )
    (net (code "33") (name "unconnected-(U110S-NC-PadG19)") (class "Default")
      (node (ref "U110") (pin "G19") (pinfunction "NC_G19") (pintype "passive+no_connect"))
    )
    (net (code "34") (name "unconnected-(U110S-NC-PadG22)") (class "Default")
      (node (ref "U110") (pin "G22") (pinfunction "NC_G22") (pintype "passive+no_connect"))
    )
    (net (code "35") (name "unconnected-(U110S-NC-PadG23)") (class "Default")
      (node (ref "U110") (pin "G23") (pinfunction "NC_G23") (pintype "passive+no_connect"))
    )
    (net (code "36") (name "unconnected-(U110S-NC-PadG24)") (class "Default")
      (node (ref "U110") (pin "G24") (pinfunction "NC_G24") (pintype "passive+no_connect"))
    )
    (net (code "37") (name "unconnected-(U110S-NC-PadH4)") (class "Default")
      (node (ref "U110") (pin "H4") (pinfunction "NC_H4") (pintype "passive+no_connect"))
    )
    (net (code "38") (name "unconnected-(U110S-NC-PadH29)") (class "Default")
      (node (ref "U110") (pin "H29") (pinfunction "NC_H29") (pintype "passive+no_connect"))
    )
    (net (code "39") (name "unconnected-(U110S-NC-PadL5)") (class "Default")
      (node (ref "U110") (pin "L5") (pinfunction "NC_L5") (pintype "passive+no_connect"))
    )
    (net (code "40") (name "unconnected-(U110S-NC-PadL28)") (class "Default")
      (node (ref "U110") (pin "L28") (pinfunction "NC_L28") (pintype "passive+no_connect"))
    )
    (net (code "41") (name "unconnected-(U110S-NC-PadV3)") (class "Default")
      (node (ref "U110") (pin "V3") (pinfunction "NC_V3") (pintype "passive+no_connect"))
    )
    (net (code "42") (name "unconnected-(U110S-NC-PadV30)") (class "Default")
      (node (ref "U110") (pin "V30") (pinfunction "NC_V30") (pintype "passive+no_connect"))
    )
    (net (code "43") (name "unconnected-(U110S-NC-PadW6)") (class "Default")
      (node (ref "U110") (pin "W6") (pinfunction "NC_W6") (pintype "passive+no_connect"))
    )
    (net (code "44") (name "unconnected-(U110S-NC-PadW27)") (class "Default")
      (node (ref "U110") (pin "W27") (pinfunction "NC_W27") (pintype "passive+no_connect"))
    )
  )
)
